# PiLoraGatewayV2_3.net
KiCad netlist of a schematic drawn in EAGLE
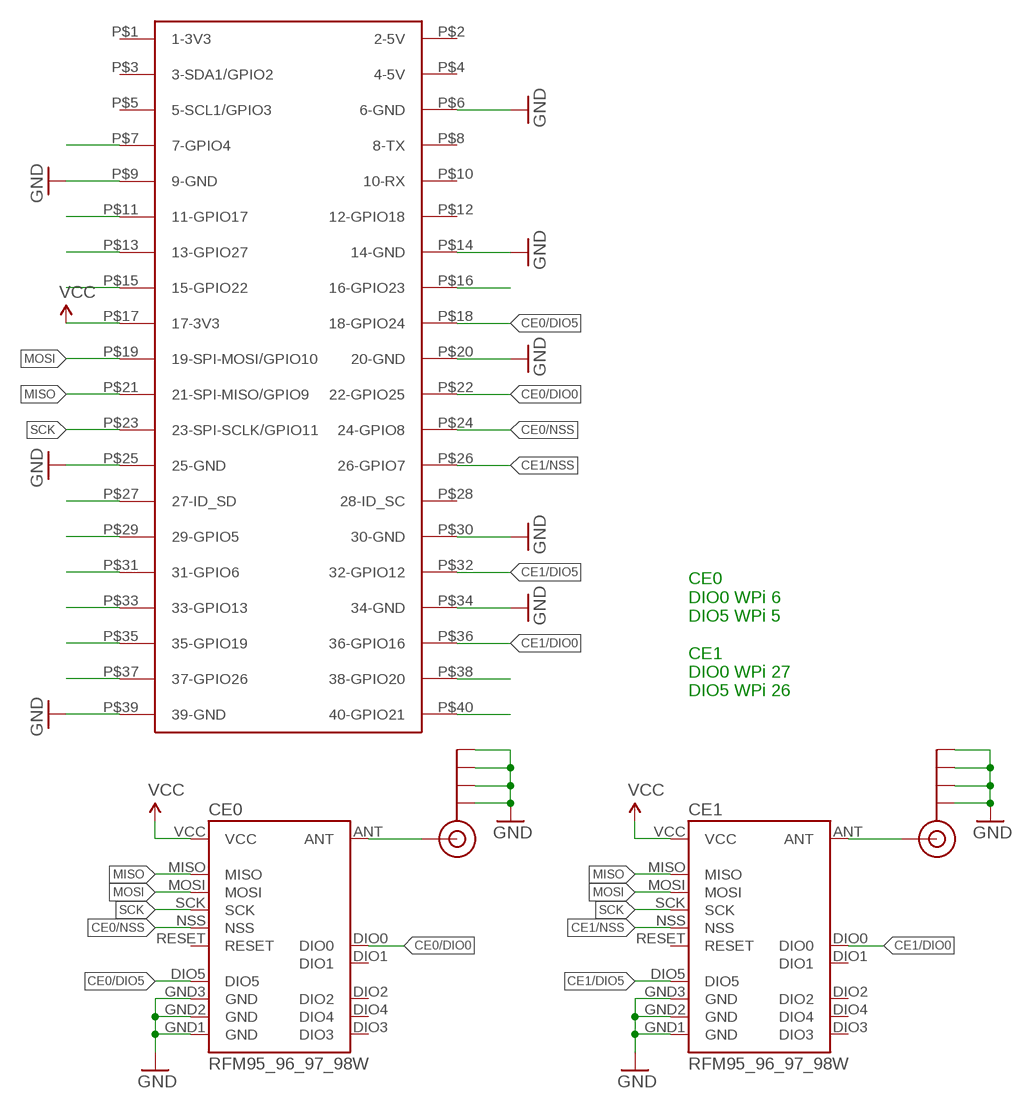
[diagram p0: schematic, sheet 1]

(export (version "E")
  (design (tool "Eeschema 10.0.6"))
  (components
    (comp (ref "CE0")
      (value "RFM95_96_97_98W")
      (footprint "eagle-import:RFM95_96_97_98W")
      (libsource (lib "eagle-import") (part "RFM95_96_97_98W"))
    )
    (comp (ref "CE1")
      (value "RFM95_96_97_98W")
      (footprint "eagle-import:RFM95_96_97_98W")
      (libsource (lib "eagle-import") (part "RFM95_96_97_98W"))
    )
    (comp (ref "J$1")
      (value "SMA_EDGE")
      (footprint "eagle-import:SMA-EDGE")
      (libsource (lib "eagle-import") (part "SMA_EDGE"))
    )
    (comp (ref "J$2")
      (value "SMA_EDGE")
      (footprint "eagle-import:SMA-EDGE")
      (libsource (lib "eagle-import") (part "SMA_EDGE"))
    )
    (comp (ref "U$1")
      (value "RASPBERRY-PI+")
      (footprint "eagle-import:RASPBERRY-PI-PLUS-CAM_NOTCH")
      (libsource (lib "eagle-import") (part "RASPBERRY-PI+"))
    )
  )
  (nets
    (net (code "1") (name "CE0{slash}DIO0") (class "Default")
      (node (ref "CE0") (pin "DIO0") (pinfunction "DIO0_DIO0") (pintype "input"))
      (node (ref "U$1") (pin "P$22") (pinfunction "22-GPIO25_P$22") (pintype "bidirectional"))
    )
    (net (code "2") (name "CE0{slash}DIO5") (class "Default")
      (node (ref "CE0") (pin "DIO5") (pinfunction "DIO5_DIO5") (pintype "input"))
      (node (ref "U$1") (pin "P$18") (pinfunction "18-GPIO24_P$18") (pintype "bidirectional"))
    )
    (net (code "3") (name "CE0{slash}NSS") (class "Default")
      (node (ref "CE0") (pin "NSS") (pinfunction "NSS_NSS") (pintype "input"))
      (node (ref "U$1") (pin "P$24") (pinfunction "24-GPIO8_P$24") (pintype "bidirectional"))
    )
    (net (code "4") (name "CE1{slash}DIO0") (class "Default")
      (node (ref "CE1") (pin "DIO0") (pinfunction "DIO0_DIO0") (pintype "input"))
      (node (ref "U$1") (pin "P$36") (pinfunction "36-GPIO16_P$36") (pintype "bidirectional"))
    )
    (net (code "5") (name "CE1{slash}DIO5") (class "Default")
      (node (ref "CE1") (pin "DIO5") (pinfunction "DIO5_DIO5") (pintype "input"))
      (node (ref "U$1") (pin "P$32") (pinfunction "32-GPIO12_P$32") (pintype "bidirectional"))
    )
    (net (code "6") (name "CE1{slash}NSS") (class "Default")
      (node (ref "CE1") (pin "NSS") (pinfunction "NSS_NSS") (pintype "input"))
      (node (ref "U$1") (pin "P$26") (pinfunction "26-GPIO7_P$26") (pintype "bidirectional"))
    )
    (net (code "7") (name "GND") (class "Default")
      (node (ref "CE0") (pin "GND1") (pinfunction "GND_GND1") (pintype "power_in"))
      (node (ref "CE0") (pin "GND2") (pinfunction "GND_GND2") (pintype "power_in"))
      (node (ref "CE0") (pin "GND3") (pinfunction "GND_GND3") (pintype "power_in"))
      (node (ref "CE1") (pin "GND1") (pinfunction "GND_GND1") (pintype "power_in"))
      (node (ref "CE1") (pin "GND2") (pinfunction "GND_GND2") (pintype "power_in"))
      (node (ref "CE1") (pin "GND3") (pinfunction "GND_GND3") (pintype "power_in"))
      (node (ref "J$1") (pin "GND@0") (pinfunction "GND_GND@0") (pintype "bidirectional"))
      (node (ref "J$1") (pin "GND@1") (pinfunction "GND_GND@1") (pintype "bidirectional"))
      (node (ref "J$1") (pin "GND@2") (pinfunction "GND_GND@2") (pintype "bidirectional"))
      (node (ref "J$1") (pin "GND@3") (pinfunction "GND_GND@3") (pintype "bidirectional"))
      (node (ref "J$2") (pin "GND@0") (pinfunction "GND_GND@0") (pintype "bidirectional"))
      (node (ref "J$2") (pin "GND@1") (pinfunction "GND_GND@1") (pintype "bidirectional"))
      (node (ref "J$2") (pin "GND@2") (pinfunction "GND_GND@2") (pintype "bidirectional"))
      (node (ref "J$2") (pin "GND@3") (pinfunction "GND_GND@3") (pintype "bidirectional"))
      (node (ref "U$1") (pin "P$14") (pinfunction "14-GND_P$14") (pintype "bidirectional"))
      (node (ref "U$1") (pin "P$20") (pinfunction "20-GND_P$20") (pintype "bidirectional"))
      (node (ref "U$1") (pin "P$25") (pinfunction "25-GND_P$25") (pintype "bidirectional"))
      (node (ref "U$1") (pin "P$30") (pinfunction "30-GND_P$30") (pintype "bidirectional"))
      (node (ref "U$1") (pin "P$34") (pinfunction "34-GND_P$34") (pintype "bidirectional"))
      (node (ref "U$1") (pin "P$39") (pinfunction "39-GND_P$39") (pintype "bidirectional"))
      (node (ref "U$1") (pin "P$6") (pinfunction "6-GND_P$6") (pintype "bidirectional"))
      (node (ref "U$1") (pin "P$9") (pinfunction "9-GND_P$9") (pintype "bidirectional"))
    )
    (net (code "8") (name "MISO") (class "Default")
      (node (ref "CE0") (pin "MISO") (pinfunction "MISO_MISO") (pintype "output"))
      (node (ref "CE1") (pin "MISO") (pinfunction "MISO_MISO") (pintype "output"))
      (node (ref "U$1") (pin "P$21") (pinfunction "21-SPI-MISO/GPIO9_P$21") (pintype "bidirectional"))
    )
    (net (code "9") (name "MOSI") (class "Default")
      (node (ref "CE0") (pin "MOSI") (pinfunction "MOSI_MOSI") (pintype "input"))
      (node (ref "CE1") (pin "MOSI") (pinfunction "MOSI_MOSI") (pintype "input"))
      (node (ref "U$1") (pin "P$19") (pinfunction "19-SPI-MOSI/GPIO10_P$19") (pintype "bidirectional"))
    )
    (net (code "10") (name "Net-(J$1-SIGNAL)") (class "Default")
      (node (ref "CE0") (pin "ANT") (pinfunction "ANT_ANT") (pintype "bidirectional"))
      (node (ref "J$1") (pin "SIG") (pinfunction "SIGNAL_SIG") (pintype "bidirectional"))
    )
    (net (code "11") (name "Net-(J$2-SIGNAL)") (class "Default")
      (node (ref "CE1") (pin "ANT") (pinfunction "ANT_ANT") (pintype "bidirectional"))
      (node (ref "J$2") (pin "SIG") (pinfunction "SIGNAL_SIG") (pintype "bidirectional"))
    )
    (net (code "12") (name "SCK") (class "Default")
      (node (ref "CE0") (pin "SCK") (pinfunction "SCK_SCK") (pintype "input"))
      (node (ref "CE1") (pin "SCK") (pinfunction "SCK_SCK") (pintype "input"))
      (node (ref "U$1") (pin "P$23") (pinfunction "23-SPI-SCLK/GPIO11_P$23") (pintype "bidirectional"))
    )
    (net (code "13") (name "VCC") (class "Default")
      (node (ref "CE0") (pin "VCC") (pinfunction "VCC_VCC") (pintype "bidirectional"))
      (node (ref "CE1") (pin "VCC") (pinfunction "VCC_VCC") (pintype "bidirectional"))
      (node (ref "U$1") (pin "P$17") (pinfunction "17-3V3_P$17") (pintype "bidirectional"))
    )
    (net (code "14") (name "unconnected-(CE0-PadDIO1)") (class "Default")
      (node (ref "CE0") (pin "DIO1") (pinfunction "DIO1_DIO1") (pintype "input"))
    )
    (net (code "15") (name "unconnected-(CE0-PadDIO2)") (class "Default")
      (node (ref "CE0") (pin "DIO2") (pinfunction "DIO2_DIO2") (pintype "bidirectional"))
    )
    (net (code "16") (name "unconnected-(CE0-PadDIO3)") (class "Default")
      (node (ref "CE0") (pin "DIO3") (pinfunction "DIO3_DIO3") (pintype "bidirectional"))
    )
    (net (code "17") (name "unconnected-(CE0-PadDIO4)") (class "Default")
      (node (ref "CE0") (pin "DIO4") (pinfunction "DIO4_DIO4") (pintype "bidirectional"))
    )
    (net (code "18") (name "unconnected-(CE0-PadRESET)") (class "Default")
      (node (ref "CE0") (pin "RESET") (pinfunction "RESET_RESET") (pintype "output"))
    )
    (net (code "19") (name "unconnected-(CE1-PadDIO1)") (class "Default")
      (node (ref "CE1") (pin "DIO1") (pinfunction "DIO1_DIO1") (pintype "input"))
    )
    (net (code "20") (name "unconnected-(CE1-PadDIO2)") (class "Default")
      (node (ref "CE1") (pin "DIO2") (pinfunction "DIO2_DIO2") (pintype "bidirectional"))
    )
    (net (code "21") (name "unconnected-(CE1-PadDIO3)") (class "Default")
      (node (ref "CE1") (pin "DIO3") (pinfunction "DIO3_DIO3") (pintype "bidirectional"))
    )
    (net (code "22") (name "unconnected-(CE1-PadDIO4)") (class "Default")
      (node (ref "CE1") (pin "DIO4") (pinfunction "DIO4_DIO4") (pintype "bidirectional"))
    )
    (net (code "23") (name "unconnected-(CE1-PadRESET)") (class "Default")
      (node (ref "CE1") (pin "RESET") (pinfunction "RESET_RESET") (pintype "output"))
    )
    (net (code "24") (name "unconnected-(U$1-1-3V3-PadP$1)") (class "Default")
      (node (ref "U$1") (pin "P$1") (pinfunction "1-3V3_P$1") (pintype "bidirectional"))
    )
    (net (code "25") (name "unconnected-(U$1-2-5V-PadP$2)") (class "Default")
      (node (ref "U$1") (pin "P$2") (pinfunction "2-5V_P$2") (pintype "bidirectional"))
    )
    (net (code "26") (name "unconnected-(U$1-3-SDA1{slash}GPIO2-PadP$3)") (class "Default")
      (node (ref "U$1") (pin "P$3") (pinfunction "3-SDA1/GPIO2_P$3") (pintype "bidirectional"))
    )
    (net (code "27") (name "unconnected-(U$1-4-5V-PadP$4)") (class "Default")
      (node (ref "U$1") (pin "P$4") (pinfunction "4-5V_P$4") (pintype "bidirectional"))
    )
    (net (code "28") (name "unconnected-(U$1-5-SCL1{slash}GPIO3-PadP$5)") (class "Default")
      (node (ref "U$1") (pin "P$5") (pinfunction "5-SCL1/GPIO3_P$5") (pintype "bidirectional"))
    )
    (net (code "29") (name "unconnected-(U$1-7-GPIO4-PadP$7)") (class "Default")
      (node (ref "U$1") (pin "P$7") (pinfunction "7-GPIO4_P$7") (pintype "bidirectional"))
    )
    (net (code "30") (name "unconnected-(U$1-8-TX-PadP$8)") (class "Default")
      (node (ref "U$1") (pin "P$8") (pinfunction "8-TX_P$8") (pintype "bidirectional"))
    )
    (net (code "31") (name "unconnected-(U$1-10-RX-PadP$10)") (class "Default")
      (node (ref "U$1") (pin "P$10") (pinfunction "10-RX_P$10") (pintype "bidirectional"))
    )
    (net (code "32") (name "unconnected-(U$1-11-GPIO17-PadP$11)") (class "Default")
      (node (ref "U$1") (pin "P$11") (pinfunction "11-GPIO17_P$11") (pintype "bidirectional"))
    )
    (net (code "33") (name "unconnected-(U$1-12-GPIO18-PadP$12)") (class "Default")
      (node (ref "U$1") (pin "P$12") (pinfunction "12-GPIO18_P$12") (pintype "bidirectional"))
    )
    (net (code "34") (name "unconnected-(U$1-13-GPIO27-PadP$13)") (class "Default")
      (node (ref "U$1") (pin "P$13") (pinfunction "13-GPIO27_P$13") (pintype "bidirectional"))
    )
    (net (code "35") (name "unconnected-(U$1-15-GPIO22-PadP$15)") (class "Default")
      (node (ref "U$1") (pin "P$15") (pinfunction "15-GPIO22_P$15") (pintype "bidirectional"))
    )
    (net (code "36") (name "unconnected-(U$1-16-GPIO23-PadP$16)") (class "Default")
      (node (ref "U$1") (pin "P$16") (pinfunction "16-GPIO23_P$16") (pintype "bidirectional"))
    )
    (net (code "37") (name "unconnected-(U$1-27-ID_SD-PadP$27)") (class "Default")
      (node (ref "U$1") (pin "P$27") (pinfunction "27-ID_SD_P$27") (pintype "bidirectional"))
    )
    (net (code "38") (name "unconnected-(U$1-28-ID_SC-PadP$28)") (class "Default")
      (node (ref "U$1") (pin "P$28") (pinfunction "28-ID_SC_P$28") (pintype "bidirectional"))
    )
    (net (code "39") (name "unconnected-(U$1-29-GPIO5-PadP$29)") (class "Default")
      (node (ref "U$1") (pin "P$29") (pinfunction "29-GPIO5_P$29") (pintype "bidirectional"))
    )
    (net (code "40") (name "unconnected-(U$1-31-GPIO6-PadP$31)") (class "Default")
      (node (ref "U$1") (pin "P$31") (pinfunction "31-GPIO6_P$31") (pintype "bidirectional"))
    )
    (net (code "41") (name "unconnected-(U$1-33-GPIO13-PadP$33)") (class "Default")
      (node (ref "U$1") (pin "P$33") (pinfunction "33-GPIO13_P$33") (pintype "bidirectional"))
    )
    (net (code "42") (name "unconnected-(U$1-35-GPIO19-PadP$35)") (class "Default")
      (node (ref "U$1") (pin "P$35") (pinfunction "35-GPIO19_P$35") (pintype "bidirectional"))
    )
    (net (code "43") (name "unconnected-(U$1-37-GPIO26-PadP$37)") (class "Default")
      (node (ref "U$1") (pin "P$37") (pinfunction "37-GPIO26_P$37") (pintype "bidirectional"))
    )
    (net (code "44") (name "unconnected-(U$1-38-GPIO20-PadP$38)") (class "Default")
      (node (ref "U$1") (pin "P$38") (pinfunction "38-GPIO20_P$38") (pintype "bidirectional"))
    )
    (net (code "45") (name "unconnected-(U$1-40-GPIO21-PadP$40)") (class "Default")
      (node (ref "U$1") (pin "P$40") (pinfunction "40-GPIO21_P$40") (pintype "bidirectional"))
    )
  )
)
